# 6LED_controller.net
KiCad netlist of a schematic drawn in EAGLE
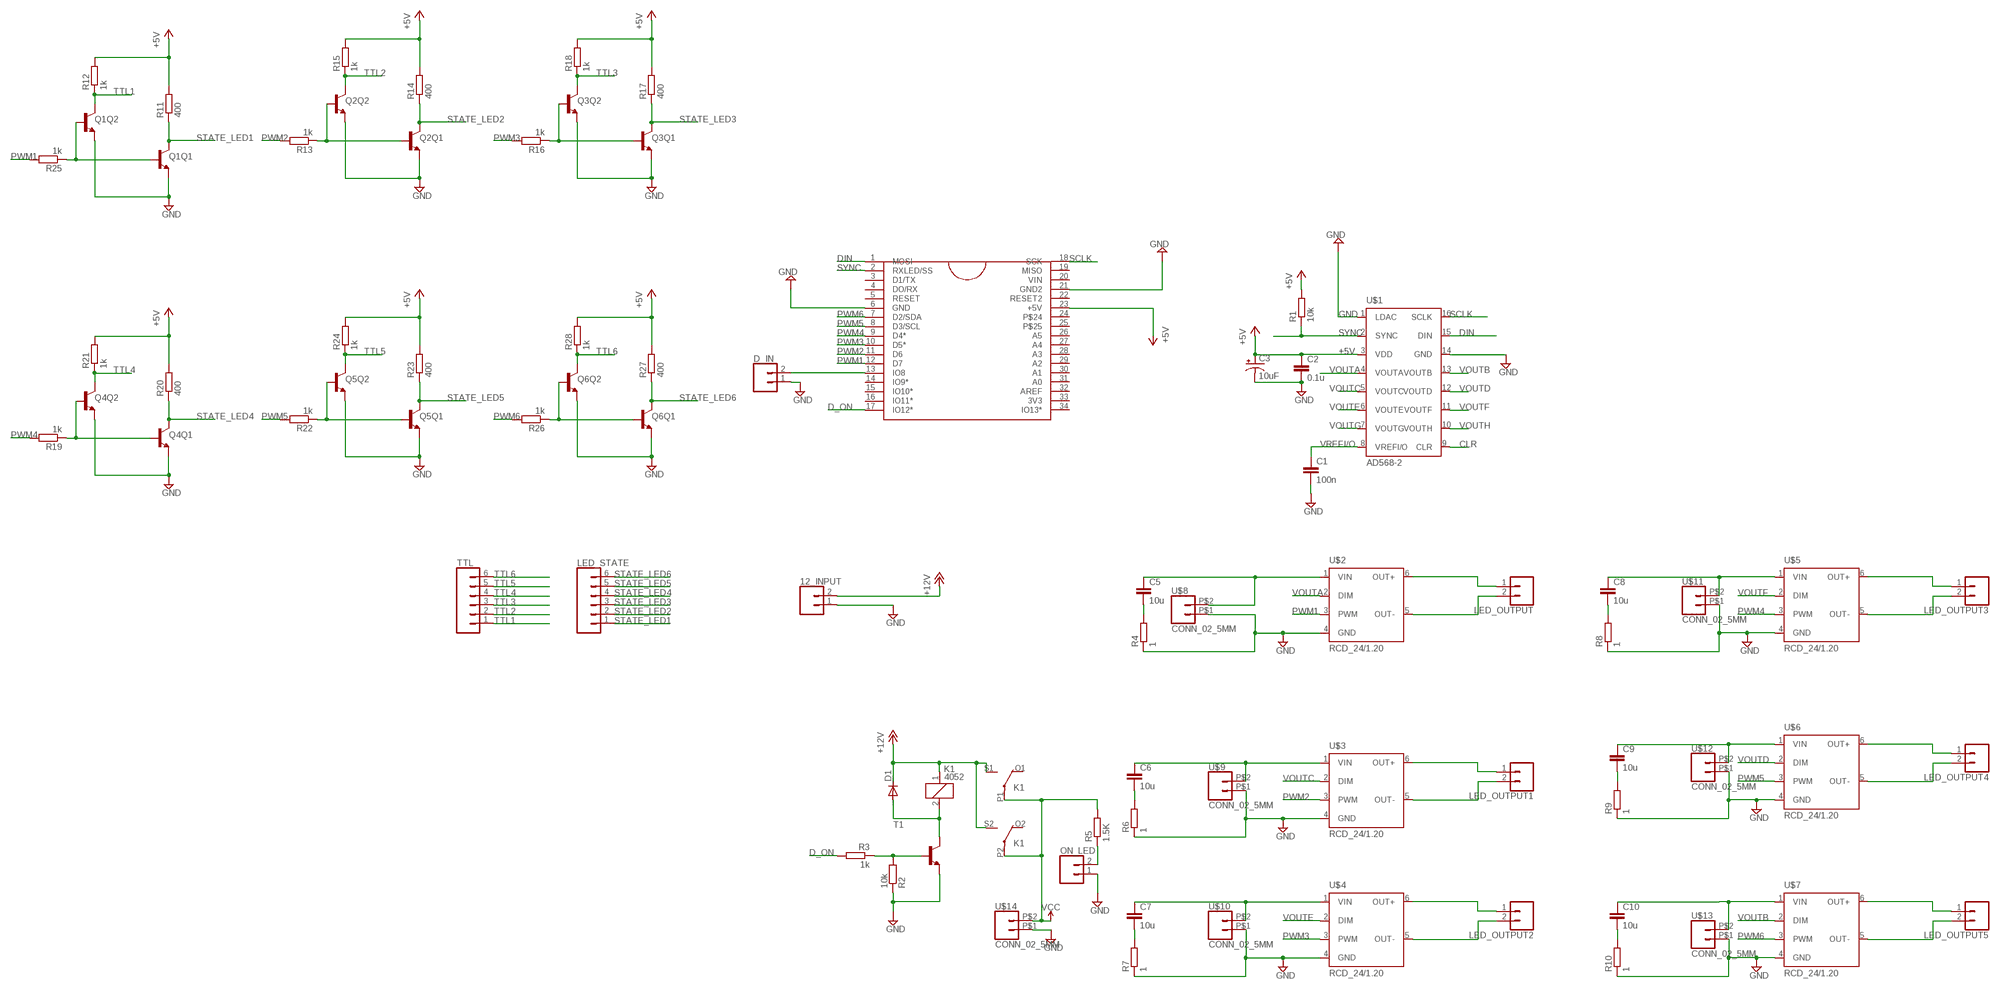
[diagram p0: schematic, sheet 1]

(export (version "E")
  (design (tool "Eeschema 10.0.6"))
  (components
    (comp (ref "12_INPUT")
      (value "CONN_023.5MM")
      (footprint "eagle-import:SCREWTERMINAL-3.5MM-2")
      (libsource (lib "eagle-import") (part "CONN_023.5MM"))
    )
    (comp (ref "C1")
      (value "100n")
      (footprint "eagle-import:C1206")
      (libsource (lib "eagle-import") (part "C-EUC1206"))
    )
    (comp (ref "C2")
      (value "0.1u")
      (footprint "eagle-import:C1206")
      (libsource (lib "eagle-import") (part "C-EUC1206"))
    )
    (comp (ref "C3")
      (value "10uF")
      (footprint "eagle-import:EIA3528")
      (libsource (lib "eagle-import") (part "10UF-POLAR-EIA3528-20V-10%(TANT)"))
    )
    (comp (ref "C5")
      (value "10u")
      (footprint "eagle-import:C1206")
      (libsource (lib "eagle-import") (part "C-EUC1206"))
    )
    (comp (ref "C6")
      (value "10u")
      (footprint "eagle-import:C1206")
      (libsource (lib "eagle-import") (part "C-EUC1206"))
    )
    (comp (ref "C7")
      (value "10u")
      (footprint "eagle-import:C1206")
      (libsource (lib "eagle-import") (part "C-EUC1206"))
    )
    (comp (ref "C8")
      (value "10u")
      (footprint "eagle-import:C1206")
      (libsource (lib "eagle-import") (part "C-EUC1206"))
    )
    (comp (ref "C9")
      (value "10u")
      (footprint "eagle-import:C1206")
      (libsource (lib "eagle-import") (part "C-EUC1206"))
    )
    (comp (ref "C10")
      (value "10u")
      (footprint "eagle-import:C1206")
      (libsource (lib "eagle-import") (part "C-EUC1206"))
    )
    (comp (ref "D1")
      (value "DIODE-DO214AC")
      (footprint "eagle-import:DO214AC")
      (libsource (lib "eagle-import") (part "DIODE-DO214AC"))
    )
    (comp (ref "D_IN")
      (value "CONN_02")
      (footprint "eagle-import:1X02")
      (libsource (lib "eagle-import") (part "CONN_02"))
    )
    (comp (ref "K1")
      (value "4052")
      (footprint "eagle-import:F4052")
      (libsource (lib "eagle-import") (part "4052"))
    )
    (comp (ref "LED_OUTPUT")
      (value "CONN_023.5MM")
      (footprint "eagle-import:SCREWTERMINAL-3.5MM-2")
      (libsource (lib "eagle-import") (part "CONN_023.5MM"))
    )
    (comp (ref "LED_OUTPUT1")
      (value "CONN_023.5MM")
      (footprint "eagle-import:SCREWTERMINAL-3.5MM-2")
      (libsource (lib "eagle-import") (part "CONN_023.5MM"))
    )
    (comp (ref "LED_OUTPUT2")
      (value "CONN_023.5MM")
      (footprint "eagle-import:SCREWTERMINAL-3.5MM-2")
      (libsource (lib "eagle-import") (part "CONN_023.5MM"))
    )
    (comp (ref "LED_OUTPUT3")
      (value "CONN_023.5MM")
      (footprint "eagle-import:SCREWTERMINAL-3.5MM-2")
      (libsource (lib "eagle-import") (part "CONN_023.5MM"))
    )
    (comp (ref "LED_OUTPUT4")
      (value "CONN_023.5MM")
      (footprint "eagle-import:SCREWTERMINAL-3.5MM-2")
      (libsource (lib "eagle-import") (part "CONN_023.5MM"))
    )
    (comp (ref "LED_OUTPUT5")
      (value "CONN_023.5MM")
      (footprint "eagle-import:SCREWTERMINAL-3.5MM-2")
      (libsource (lib "eagle-import") (part "CONN_023.5MM"))
    )
    (comp (ref "LED_STATE")
      (value "CONN_06POLAR")
      (footprint "eagle-import:MOLEX-1X6")
      (libsource (lib "eagle-import") (part "CONN_06POLAR"))
    )
    (comp (ref "ON_LED")
      (value "CONN_02")
      (footprint "eagle-import:1X02")
      (libsource (lib "eagle-import") (part "CONN_02"))
    )
    (comp (ref "Q1")
      (value "TRANS_NPN_DUAL_NSM4002-MBT3904DW1T1")
      (footprint "eagle-import:SC70-6")
      (libsource (lib "eagle-import") (part "TRANS_NPN_DUAL_NSM4002-MBT3904DW1T1"))
    )
    (comp (ref "Q2")
      (value "TRANS_NPN_DUAL_NSM4002-MBT3904DW1T1")
      (footprint "eagle-import:SC70-6")
      (libsource (lib "eagle-import") (part "TRANS_NPN_DUAL_NSM4002-MBT3904DW1T1"))
    )
    (comp (ref "Q3")
      (value "TRANS_NPN_DUAL_NSM4002-MBT3904DW1T1")
      (footprint "eagle-import:SC70-6")
      (libsource (lib "eagle-import") (part "TRANS_NPN_DUAL_NSM4002-MBT3904DW1T1"))
    )
    (comp (ref "Q4")
      (value "TRANS_NPN_DUAL_NSM4002-MBT3904DW1T1")
      (footprint "eagle-import:SC70-6")
      (libsource (lib "eagle-import") (part "TRANS_NPN_DUAL_NSM4002-MBT3904DW1T1"))
    )
    (comp (ref "Q5")
      (value "TRANS_NPN_DUAL_NSM4002-MBT3904DW1T1")
      (footprint "eagle-import:SC70-6")
      (libsource (lib "eagle-import") (part "TRANS_NPN_DUAL_NSM4002-MBT3904DW1T1"))
    )
    (comp (ref "Q6")
      (value "TRANS_NPN_DUAL_NSM4002-MBT3904DW1T1")
      (footprint "eagle-import:SC70-6")
      (libsource (lib "eagle-import") (part "TRANS_NPN_DUAL_NSM4002-MBT3904DW1T1"))
    )
    (comp (ref "R1")
      (value "10k")
      (footprint "eagle-import:R1206")
      (libsource (lib "eagle-import") (part "R-EU_R1206"))
    )
    (comp (ref "R2")
      (value "10k")
      (footprint "eagle-import:R1206")
      (libsource (lib "eagle-import") (part "R-EU_R1206"))
    )
    (comp (ref "R3")
      (value "1k")
      (footprint "eagle-import:R0805")
      (libsource (lib "eagle-import") (part "R-EU_R0805"))
    )
    (comp (ref "R4")
      (value "1")
      (footprint "eagle-import:R2512")
      (libsource (lib "eagle-import") (part "R-EU_R2512"))
    )
    (comp (ref "R5")
      (value "1.5K")
      (footprint "eagle-import:R0805")
      (libsource (lib "eagle-import") (part "R-EU_R0805"))
    )
    (comp (ref "R6")
      (value "1")
      (footprint "eagle-import:R2512")
      (libsource (lib "eagle-import") (part "R-EU_R2512"))
    )
    (comp (ref "R7")
      (value "1")
      (footprint "eagle-import:R2512")
      (libsource (lib "eagle-import") (part "R-EU_R2512"))
    )
    (comp (ref "R8")
      (value "1")
      (footprint "eagle-import:R2512")
      (libsource (lib "eagle-import") (part "R-EU_R2512"))
    )
    (comp (ref "R9")
      (value "1")
      (footprint "eagle-import:R2512")
      (libsource (lib "eagle-import") (part "R-EU_R2512"))
    )
    (comp (ref "R10")
      (value "1")
      (footprint "eagle-import:R2512")
      (libsource (lib "eagle-import") (part "R-EU_R2512"))
    )
    (comp (ref "R11")
      (value "400")
      (footprint "eagle-import:R0805")
      (libsource (lib "eagle-import") (part "R-EU_R0805"))
    )
    (comp (ref "R12")
      (value "1k")
      (footprint "eagle-import:R0805")
      (libsource (lib "eagle-import") (part "R-EU_R0805"))
    )
    (comp (ref "R13")
      (value "1k")
      (footprint "eagle-import:R0805")
      (libsource (lib "eagle-import") (part "R-EU_R0805"))
    )
    (comp (ref "R14")
      (value "400")
      (footprint "eagle-import:R0805")
      (libsource (lib "eagle-import") (part "R-EU_R0805"))
    )
    (comp (ref "R15")
      (value "1k")
      (footprint "eagle-import:R0805")
      (libsource (lib "eagle-import") (part "R-EU_R0805"))
    )
    (comp (ref "R16")
      (value "1k")
      (footprint "eagle-import:R0805")
      (libsource (lib "eagle-import") (part "R-EU_R0805"))
    )
    (comp (ref "R17")
      (value "400")
      (footprint "eagle-import:R0805")
      (libsource (lib "eagle-import") (part "R-EU_R0805"))
    )
    (comp (ref "R18")
      (value "1k")
      (footprint "eagle-import:R0805")
      (libsource (lib "eagle-import") (part "R-EU_R0805"))
    )
    (comp (ref "R19")
      (value "1k")
      (footprint "eagle-import:R0805")
      (libsource (lib "eagle-import") (part "R-EU_R0805"))
    )
    (comp (ref "R20")
      (value "400")
      (footprint "eagle-import:R0805")
      (libsource (lib "eagle-import") (part "R-EU_R0805"))
    )
    (comp (ref "R21")
      (value "1k")
      (footprint "eagle-import:R0805")
      (libsource (lib "eagle-import") (part "R-EU_R0805"))
    )
    (comp (ref "R22")
      (value "1k")
      (footprint "eagle-import:R0805")
      (libsource (lib "eagle-import") (part "R-EU_R0805"))
    )
    (comp (ref "R23")
      (value "400")
      (footprint "eagle-import:R0805")
      (libsource (lib "eagle-import") (part "R-EU_R0805"))
    )
    (comp (ref "R24")
      (value "1k")
      (footprint "eagle-import:R0805")
      (libsource (lib "eagle-import") (part "R-EU_R0805"))
    )
    (comp (ref "R25")
      (value "1k")
      (footprint "eagle-import:R0805")
      (libsource (lib "eagle-import") (part "R-EU_R0805"))
    )
    (comp (ref "R26")
      (value "1k")
      (footprint "eagle-import:R0805")
      (libsource (lib "eagle-import") (part "R-EU_R0805"))
    )
    (comp (ref "R27")
      (value "400")
      (footprint "eagle-import:R0805")
      (libsource (lib "eagle-import") (part "R-EU_R0805"))
    )
    (comp (ref "R28")
      (value "1k")
      (footprint "eagle-import:R0805")
      (libsource (lib "eagle-import") (part "R-EU_R0805"))
    )
    (comp (ref "T1")
      (value "-NPN-SOT223")
      (footprint "eagle-import:SOT223")
      (libsource (lib "eagle-import") (part "-NPN-SOT223"))
    )
    (comp (ref "TTL")
      (value "CONN_06POLAR")
      (footprint "eagle-import:MOLEX-1X6")
      (libsource (lib "eagle-import") (part "CONN_06POLAR"))
    )
    (comp (ref "U$1")
      (value "AD568-2")
      (footprint "eagle-import:TSSOP-16")
      (libsource (lib "eagle-import") (part "AD568-2"))
    )
    (comp (ref "U$2")
      (value "RCD_24/1.20")
      (footprint "eagle-import:RCD-24_W_X3")
      (libsource (lib "eagle-import") (part "RCD_24/1.20"))
    )
    (comp (ref "U$3")
      (value "RCD_24/1.20")
      (footprint "eagle-import:RCD-24_W_X3")
      (libsource (lib "eagle-import") (part "RCD_24/1.20"))
    )
    (comp (ref "U$4")
      (value "RCD_24/1.20")
      (footprint "eagle-import:RCD-24_W_X3")
      (libsource (lib "eagle-import") (part "RCD_24/1.20"))
    )
    (comp (ref "U$5")
      (value "RCD_24/1.20")
      (footprint "eagle-import:RCD-24_W_X3")
      (libsource (lib "eagle-import") (part "RCD_24/1.20"))
    )
    (comp (ref "U$6")
      (value "RCD_24/1.20")
      (footprint "eagle-import:RCD-24_W_X3")
      (libsource (lib "eagle-import") (part "RCD_24/1.20"))
    )
    (comp (ref "U$7")
      (value "RCD_24/1.20")
      (footprint "eagle-import:RCD-24_W_X3")
      (libsource (lib "eagle-import") (part "RCD_24/1.20"))
    )
    (comp (ref "U$8")
      (value "CONN_02_5MM")
      (footprint "eagle-import:1X02_BIG_5MM")
      (libsource (lib "eagle-import") (part "CONN_02_5MM"))
    )
    (comp (ref "U$9")
      (value "CONN_02_5MM")
      (footprint "eagle-import:1X02_BIG_5MM")
      (libsource (lib "eagle-import") (part "CONN_02_5MM"))
    )
    (comp (ref "U$10")
      (value "CONN_02_5MM")
      (footprint "eagle-import:1X02_BIG_5MM")
      (libsource (lib "eagle-import") (part "CONN_02_5MM"))
    )
    (comp (ref "U$11")
      (value "CONN_02_5MM")
      (footprint "eagle-import:1X02_BIG_5MM")
      (libsource (lib "eagle-import") (part "CONN_02_5MM"))
    )
    (comp (ref "U$12")
      (value "CONN_02_5MM")
      (footprint "eagle-import:1X02_BIG_5MM")
      (libsource (lib "eagle-import") (part "CONN_02_5MM"))
    )
    (comp (ref "U$13")
      (value "CONN_02_5MM")
      (footprint "eagle-import:1X02_BIG_5MM")
      (libsource (lib "eagle-import") (part "CONN_02_5MM"))
    )
    (comp (ref "U$14")
      (value "CONN_02_5MM")
      (footprint "eagle-import:1X02_BIG_5MM")
      (libsource (lib "eagle-import") (part "CONN_02_5MM"))
    )
    (comp (ref "U$20")
      (value "ARDUINO_MICRO")
      (footprint "eagle-import:ARDUINO_MICRO_PADS")
      (fields (field (name "SPICEPREFIX") "X"))
      (libsource (lib "eagle-import") (part "ARDUINO_MICRO"))
    )
  )
  (nets
    (net (code "1") (name "+5V") (class "Default")
      (node (ref "C2") (pin "1") (pinfunction "1_1") (pintype "passive"))
      (node (ref "C3") (pin "A") (pinfunction "+_A") (pintype "passive"))
      (node (ref "R1") (pin "2") (pinfunction "2_2") (pintype "passive"))
      (node (ref "R11") (pin "2") (pinfunction "2_2") (pintype "passive"))
      (node (ref "R12") (pin "2") (pinfunction "2_2") (pintype "passive"))
      (node (ref "R14") (pin "2") (pinfunction "2_2") (pintype "passive"))
      (node (ref "R15") (pin "2") (pinfunction "2_2") (pintype "passive"))
      (node (ref "R17") (pin "2") (pinfunction "2_2") (pintype "passive"))
      (node (ref "R18") (pin "2") (pinfunction "2_2") (pintype "passive"))
      (node (ref "R20") (pin "2") (pinfunction "2_2") (pintype "passive"))
      (node (ref "R21") (pin "2") (pinfunction "2_2") (pintype "passive"))
      (node (ref "R23") (pin "2") (pinfunction "2_2") (pintype "passive"))
      (node (ref "R24") (pin "2") (pinfunction "2_2") (pintype "passive"))
      (node (ref "R27") (pin "2") (pinfunction "2_2") (pintype "passive"))
      (node (ref "R28") (pin "2") (pinfunction "2_2") (pintype "passive"))
      (node (ref "U$1") (pin "3") (pinfunction "VDD_3") (pintype "power_in"))
      (node (ref "U$20") (pin "23") (pinfunction "+5V_23") (pintype "bidirectional"))
    )
    (net (code "2") (name "+12V") (class "Default")
      (node (ref "12_INPUT") (pin "2") (pinfunction "2_2") (pintype "passive"))
      (node (ref "D1") (pin "C") (pinfunction "C_C") (pintype "passive"))
      (node (ref "K1") (pin "1") (pinfunction "1_1") (pintype "passive"))
      (node (ref "K1") (pin "S1") (pinfunction "S_S1") (pintype "passive"))
      (node (ref "K1") (pin "S2") (pinfunction "S_S2") (pintype "passive"))
    )
    (net (code "3") (name "/CLR") (class "Default")
      (node (ref "U$1") (pin "9") (pinfunction "CLR_9") (pintype "output"))
    )
    (net (code "4") (name "/DIN") (class "Default")
      (node (ref "U$1") (pin "15") (pinfunction "DIN_15") (pintype "input"))
      (node (ref "U$20") (pin "1") (pinfunction "MOSI_1") (pintype "bidirectional"))
    )
    (net (code "5") (name "/D_ON") (class "Default")
      (node (ref "R3") (pin "2") (pinfunction "2_2") (pintype "passive"))
      (node (ref "U$20") (pin "17") (pinfunction "IO12*_17") (pintype "bidirectional"))
    )
    (net (code "6") (name "/PWM1") (class "Default")
      (node (ref "R25") (pin "2") (pinfunction "2_2") (pintype "passive"))
      (node (ref "U$2") (pin "3") (pinfunction "PWM_3") (pintype "passive"))
      (node (ref "U$20") (pin "12") (pinfunction "D7_12") (pintype "bidirectional"))
    )
    (net (code "7") (name "/PWM2") (class "Default")
      (node (ref "R13") (pin "2") (pinfunction "2_2") (pintype "passive"))
      (node (ref "U$20") (pin "11") (pinfunction "D6_11") (pintype "bidirectional"))
      (node (ref "U$3") (pin "3") (pinfunction "PWM_3") (pintype "passive"))
    )
    (net (code "8") (name "/PWM3") (class "Default")
      (node (ref "R16") (pin "2") (pinfunction "2_2") (pintype "passive"))
      (node (ref "U$20") (pin "10") (pinfunction "D5*_10") (pintype "bidirectional"))
      (node (ref "U$4") (pin "3") (pinfunction "PWM_3") (pintype "passive"))
    )
    (net (code "9") (name "/PWM4") (class "Default")
      (node (ref "R19") (pin "2") (pinfunction "2_2") (pintype "passive"))
      (node (ref "U$20") (pin "9") (pinfunction "D4*_9") (pintype "bidirectional"))
      (node (ref "U$5") (pin "3") (pinfunction "PWM_3") (pintype "passive"))
    )
    (net (code "10") (name "/PWM5") (class "Default")
      (node (ref "R22") (pin "2") (pinfunction "2_2") (pintype "passive"))
      (node (ref "U$20") (pin "8") (pinfunction "D3/SCL_8") (pintype "bidirectional"))
      (node (ref "U$6") (pin "3") (pinfunction "PWM_3") (pintype "passive"))
    )
    (net (code "11") (name "/PWM6") (class "Default")
      (node (ref "R26") (pin "2") (pinfunction "2_2") (pintype "passive"))
      (node (ref "U$20") (pin "7") (pinfunction "D2/SDA_7") (pintype "bidirectional"))
      (node (ref "U$7") (pin "3") (pinfunction "PWM_3") (pintype "passive"))
    )
    (net (code "12") (name "/SCLK") (class "Default")
      (node (ref "U$1") (pin "16") (pinfunction "SCLK_16") (pintype "input"))
      (node (ref "U$20") (pin "18") (pinfunction "SCK_18") (pintype "bidirectional"))
    )
    (net (code "13") (name "/STATE_LED1") (class "Default")
      (node (ref "LED_STATE") (pin "1") (pinfunction "1_1") (pintype "passive"))
      (node (ref "Q1") (pin "3") (pinfunction "C_3") (pintype "passive"))
      (node (ref "R11") (pin "1") (pinfunction "1_1") (pintype "passive"))
    )
    (net (code "14") (name "/STATE_LED2") (class "Default")
      (node (ref "LED_STATE") (pin "2") (pinfunction "2_2") (pintype "passive"))
      (node (ref "Q2") (pin "3") (pinfunction "C_3") (pintype "passive"))
      (node (ref "R14") (pin "1") (pinfunction "1_1") (pintype "passive"))
    )
    (net (code "15") (name "/STATE_LED3") (class "Default")
      (node (ref "LED_STATE") (pin "3") (pinfunction "3_3") (pintype "passive"))
      (node (ref "Q3") (pin "3") (pinfunction "C_3") (pintype "passive"))
      (node (ref "R17") (pin "1") (pinfunction "1_1") (pintype "passive"))
    )
    (net (code "16") (name "/STATE_LED4") (class "Default")
      (node (ref "LED_STATE") (pin "4") (pinfunction "4_4") (pintype "passive"))
      (node (ref "Q4") (pin "3") (pinfunction "C_3") (pintype "passive"))
      (node (ref "R20") (pin "1") (pinfunction "1_1") (pintype "passive"))
    )
    (net (code "17") (name "/STATE_LED5") (class "Default")
      (node (ref "LED_STATE") (pin "5") (pinfunction "5_5") (pintype "passive"))
      (node (ref "Q5") (pin "3") (pinfunction "C_3") (pintype "passive"))
      (node (ref "R23") (pin "1") (pinfunction "1_1") (pintype "passive"))
    )
    (net (code "18") (name "/STATE_LED6") (class "Default")
      (node (ref "LED_STATE") (pin "6") (pinfunction "6_6") (pintype "passive"))
      (node (ref "Q6") (pin "3") (pinfunction "C_3") (pintype "passive"))
      (node (ref "R27") (pin "1") (pinfunction "1_1") (pintype "passive"))
    )
    (net (code "19") (name "/SYNC") (class "Default")
      (node (ref "R1") (pin "1") (pinfunction "1_1") (pintype "passive"))
      (node (ref "U$1") (pin "2") (pinfunction "SYNC_2") (pintype "input"))
      (node (ref "U$20") (pin "2") (pinfunction "RXLED/SS_2") (pintype "bidirectional"))
    )
    (net (code "20") (name "/TTL1") (class "Default")
      (node (ref "Q1") (pin "6") (pinfunction "C_6") (pintype "passive"))
      (node (ref "R12") (pin "1") (pinfunction "1_1") (pintype "passive"))
      (node (ref "TTL") (pin "1") (pinfunction "1_1") (pintype "passive"))
    )
    (net (code "21") (name "/TTL2") (class "Default")
      (node (ref "Q2") (pin "6") (pinfunction "C_6") (pintype "passive"))
      (node (ref "R15") (pin "1") (pinfunction "1_1") (pintype "passive"))
      (node (ref "TTL") (pin "2") (pinfunction "2_2") (pintype "passive"))
    )
    (net (code "22") (name "/TTL3") (class "Default")
      (node (ref "Q3") (pin "6") (pinfunction "C_6") (pintype "passive"))
      (node (ref "R18") (pin "1") (pinfunction "1_1") (pintype "passive"))
      (node (ref "TTL") (pin "3") (pinfunction "3_3") (pintype "passive"))
    )
    (net (code "23") (name "/TTL4") (class "Default")
      (node (ref "Q4") (pin "6") (pinfunction "C_6") (pintype "passive"))
      (node (ref "R21") (pin "1") (pinfunction "1_1") (pintype "passive"))
      (node (ref "TTL") (pin "4") (pinfunction "4_4") (pintype "passive"))
    )
    (net (code "24") (name "/TTL5") (class "Default")
      (node (ref "Q5") (pin "6") (pinfunction "C_6") (pintype "passive"))
      (node (ref "R24") (pin "1") (pinfunction "1_1") (pintype "passive"))
      (node (ref "TTL") (pin "5") (pinfunction "5_5") (pintype "passive"))
    )
    (net (code "25") (name "/TTL6") (class "Default")
      (node (ref "Q6") (pin "6") (pinfunction "C_6") (pintype "passive"))
      (node (ref "R28") (pin "1") (pinfunction "1_1") (pintype "passive"))
      (node (ref "TTL") (pin "6") (pinfunction "6_6") (pintype "passive"))
    )
    (net (code "26") (name "/VOUTA") (class "Default")
      (node (ref "U$1") (pin "4") (pinfunction "VOUTA_4") (pintype "output"))
      (node (ref "U$2") (pin "2") (pinfunction "DIM_2") (pintype "passive"))
    )
    (net (code "27") (name "/VOUTB") (class "Default")
      (node (ref "U$1") (pin "13") (pinfunction "VOUTB_13") (pintype "output"))
      (node (ref "U$7") (pin "2") (pinfunction "DIM_2") (pintype "passive"))
    )
    (net (code "28") (name "/VOUTC") (class "Default")
      (node (ref "U$1") (pin "5") (pinfunction "VOUTC_5") (pintype "output"))
      (node (ref "U$3") (pin "2") (pinfunction "DIM_2") (pintype "passive"))
    )
    (net (code "29") (name "/VOUTD") (class "Default")
      (node (ref "U$1") (pin "12") (pinfunction "VOUTD_12") (pintype "output"))
      (node (ref "U$6") (pin "2") (pinfunction "DIM_2") (pintype "passive"))
    )
    (net (code "30") (name "/VOUTE") (class "Default")
      (node (ref "U$1") (pin "6") (pinfunction "VOUTE_6") (pintype "output"))
      (node (ref "U$4") (pin "2") (pinfunction "DIM_2") (pintype "passive"))
    )
    (net (code "31") (name "/VOUTF") (class "Default")
      (node (ref "U$1") (pin "11") (pinfunction "VOUTF_11") (pintype "output"))
      (node (ref "U$5") (pin "2") (pinfunction "DIM_2") (pintype "passive"))
    )
    (net (code "32") (name "/VOUTG") (class "Default")
      (node (ref "U$1") (pin "7") (pinfunction "VOUTG_7") (pintype "output"))
    )
    (net (code "33") (name "/VOUTH") (class "Default")
      (node (ref "U$1") (pin "10") (pinfunction "VOUTH_10") (pintype "output"))
    )
    (net (code "34") (name "/VREFI{slash}O") (class "Default")
      (node (ref "C1") (pin "1") (pinfunction "1_1") (pintype "passive"))
      (node (ref "U$1") (pin "8") (pinfunction "VREFI/O_8") (pintype "output"))
    )
    (net (code "35") (name "GND") (class "Default")
      (node (ref "12_INPUT") (pin "1") (pinfunction "1_1") (pintype "passive"))
      (node (ref "C1") (pin "2") (pinfunction "2_2") (pintype "passive"))
      (node (ref "C2") (pin "2") (pinfunction "2_2") (pintype "passive"))
      (node (ref "C3") (pin "C") (pinfunction "-_C") (pintype "passive"))
      (node (ref "D_IN") (pin "1") (pinfunction "1_1") (pintype "passive"))
      (node (ref "ON_LED") (pin "1") (pinfunction "1_1") (pintype "passive"))
      (node (ref "Q1") (pin "1") (pinfunction "E_1") (pintype "passive"))
      (node (ref "Q1") (pin "4") (pinfunction "E_4") (pintype "passive"))
      (node (ref "Q2") (pin "1") (pinfunction "E_1") (pintype "passive"))
      (node (ref "Q2") (pin "4") (pinfunction "E_4") (pintype "passive"))
      (node (ref "Q3") (pin "1") (pinfunction "E_1") (pintype "passive"))
      (node (ref "Q3") (pin "4") (pinfunction "E_4") (pintype "passive"))
      (node (ref "Q4") (pin "1") (pinfunction "E_1") (pintype "passive"))
      (node (ref "Q4") (pin "4") (pinfunction "E_4") (pintype "passive"))
      (node (ref "Q5") (pin "1") (pinfunction "E_1") (pintype "passive"))
      (node (ref "Q5") (pin "4") (pinfunction "E_4") (pintype "passive"))
      (node (ref "Q6") (pin "1") (pinfunction "E_1") (pintype "passive"))
      (node (ref "Q6") (pin "4") (pinfunction "E_4") (pintype "passive"))
      (node (ref "R10") (pin "1") (pinfunction "1_1") (pintype "passive"))
      (node (ref "R2") (pin "1") (pinfunction "1_1") (pintype "passive"))
      (node (ref "R4") (pin "1") (pinfunction "1_1") (pintype "passive"))
      (node (ref "R6") (pin "1") (pinfunction "1_1") (pintype "passive"))
      (node (ref "R7") (pin "1") (pinfunction "1_1") (pintype "passive"))
      (node (ref "R8") (pin "1") (pinfunction "1_1") (pintype "passive"))
      (node (ref "R9") (pin "1") (pinfunction "1_1") (pintype "passive"))
      (node (ref "T1") (pin "3") (pinfunction "E_3") (pintype "passive"))
      (node (ref "U$1") (pin "1") (pinfunction "LDAC_1") (pintype "bidirectional"))
      (node (ref "U$1") (pin "14") (pinfunction "GND_14") (pintype "power_in"))
      (node (ref "U$10") (pin "P$1") (pinfunction "1_P$1") (pintype "passive"))
      (node (ref "U$11") (pin "P$1") (pinfunction "1_P$1") (pintype "passive"))
      (node (ref "U$12") (pin "P$1") (pinfunction "1_P$1") (pintype "passive"))
      (node (ref "U$13") (pin "P$1") (pinfunction "1_P$1") (pintype "passive"))
      (node (ref "U$14") (pin "P$1") (pinfunction "1_P$1") (pintype "passive"))
      (node (ref "U$2") (pin "4") (pinfunction "GND_4") (pintype "power_in"))
      (node (ref "U$20") (pin "21") (pinfunction "GND2_21") (pintype "power_in"))
      (node (ref "U$20") (pin "6") (pinfunction "GND_6") (pintype "power_in"))
      (node (ref "U$3") (pin "4") (pinfunction "GND_4") (pintype "power_in"))
      (node (ref "U$4") (pin "4") (pinfunction "GND_4") (pintype "power_in"))
      (node (ref "U$5") (pin "4") (pinfunction "GND_4") (pintype "power_in"))
      (node (ref "U$6") (pin "4") (pinfunction "GND_4") (pintype "power_in"))
      (node (ref "U$7") (pin "4") (pinfunction "GND_4") (pintype "power_in"))
      (node (ref "U$8") (pin "P$1") (pinfunction "1_P$1") (pintype "passive"))
      (node (ref "U$9") (pin "P$1") (pinfunction "1_P$1") (pintype "passive"))
    )
    (net (code "36") (name "Net-(C5-Pad2)") (class "Default")
      (node (ref "C5") (pin "2") (pinfunction "2_2") (pintype "passive"))
      (node (ref "R4") (pin "2") (pinfunction "2_2") (pintype "passive"))
    )
    (net (code "37") (name "Net-(C6-Pad2)") (class "Default")
      (node (ref "C6") (pin "2") (pinfunction "2_2") (pintype "passive"))
      (node (ref "R6") (pin "2") (pinfunction "2_2") (pintype "passive"))
    )
    (net (code "38") (name "Net-(C7-Pad2)") (class "Default")
      (node (ref "C7") (pin "2") (pinfunction "2_2") (pintype "passive"))
      (node (ref "R7") (pin "2") (pinfunction "2_2") (pintype "passive"))
    )
    (net (code "39") (name "Net-(C8-Pad2)") (class "Default")
      (node (ref "C8") (pin "2") (pinfunction "2_2") (pintype "passive"))
      (node (ref "R8") (pin "2") (pinfunction "2_2") (pintype "passive"))
    )
    (net (code "40") (name "Net-(C9-Pad2)") (class "Default")
      (node (ref "C9") (pin "2") (pinfunction "2_2") (pintype "passive"))
      (node (ref "R9") (pin "2") (pinfunction "2_2") (pintype "passive"))
    )
    (net (code "41") (name "Net-(C10-Pad2)") (class "Default")
      (node (ref "C10") (pin "2") (pinfunction "2_2") (pintype "passive"))
      (node (ref "R10") (pin "2") (pinfunction "2_2") (pintype "passive"))
    )
    (net (code "42") (name "Net-(ON_LED-Pad2)") (class "Default")
      (node (ref "ON_LED") (pin "2") (pinfunction "2_2") (pintype "passive"))
      (node (ref "R5") (pin "1") (pinfunction "1_1") (pintype "passive"))
    )
    (net (code "43") (name "Net-(Q1A-B)") (class "Default")
      (node (ref "Q1") (pin "2") (pinfunction "B_2") (pintype "passive"))
      (node (ref "Q1") (pin "5") (pinfunction "B_5") (pintype "passive"))
      (node (ref "R25") (pin "1") (pinfunction "1_1") (pintype "passive"))
    )
    (net (code "44") (name "Net-(Q2A-B)") (class "Default")
      (node (ref "Q2") (pin "2") (pinfunction "B_2") (pintype "passive"))
      (node (ref "Q2") (pin "5") (pinfunction "B_5") (pintype "passive"))
      (node (ref "R13") (pin "1") (pinfunction "1_1") (pintype "passive"))
    )
    (net (code "45") (name "Net-(Q3A-B)") (class "Default")
      (node (ref "Q3") (pin "2") (pinfunction "B_2") (pintype "passive"))
      (node (ref "Q3") (pin "5") (pinfunction "B_5") (pintype "passive"))
      (node (ref "R16") (pin "1") (pinfunction "1_1") (pintype "passive"))
    )
    (net (code "46") (name "Net-(Q4A-B)") (class "Default")
      (node (ref "Q4") (pin "2") (pinfunction "B_2") (pintype "passive"))
      (node (ref "Q4") (pin "5") (pinfunction "B_5") (pintype "passive"))
      (node (ref "R19") (pin "1") (pinfunction "1_1") (pintype "passive"))
    )
    (net (code "47") (name "Net-(Q5A-B)") (class "Default")
      (node (ref "Q5") (pin "2") (pinfunction "B_2") (pintype "passive"))
      (node (ref "Q5") (pin "5") (pinfunction "B_5") (pintype "passive"))
      (node (ref "R22") (pin "1") (pinfunction "1_1") (pintype "passive"))
    )
    (net (code "48") (name "Net-(Q6A-B)") (class "Default")
      (node (ref "Q6") (pin "2") (pinfunction "B_2") (pintype "passive"))
      (node (ref "Q6") (pin "5") (pinfunction "B_5") (pintype "passive"))
      (node (ref "R26") (pin "1") (pinfunction "1_1") (pintype "passive"))
    )
    (net (code "49") (name "Net-(T1-B)") (class "Default")
      (node (ref "R2") (pin "2") (pinfunction "2_2") (pintype "passive"))
      (node (ref "R3") (pin "1") (pinfunction "1_1") (pintype "passive"))
      (node (ref "T1") (pin "1") (pinfunction "B_1") (pintype "passive"))
    )
    (net (code "50") (name "Net-(T1-C)") (class "Default")
      (node (ref "D1") (pin "A") (pinfunction "A_A") (pintype "passive"))
      (node (ref "K1") (pin "2") (pinfunction "2_2") (pintype "passive"))
      (node (ref "T1") (pin "4") (pinfunction "C_4") (pintype "passive"))
    )
    (net (code "51") (name "Net-(U$2-OUT+)") (class "Default")
      (node (ref "LED_OUTPUT") (pin "1") (pinfunction "1_1") (pintype "passive"))
      (node (ref "U$2") (pin "6") (pinfunction "OUT+_6") (pintype "output"))
    )
    (net (code "52") (name "Net-(U$2-OUT-)") (class "Default")
      (node (ref "LED_OUTPUT") (pin "2") (pinfunction "2_2") (pintype "passive"))
      (node (ref "U$2") (pin "5") (pinfunction "OUT-_5") (pintype "output"))
    )
    (net (code "53") (name "Net-(U$2-VIN)") (class "Default")
      (node (ref "C5") (pin "1") (pinfunction "1_1") (pintype "passive"))
      (node (ref "U$2") (pin "1") (pinfunction "VIN_1") (pintype "input"))
      (node (ref "U$8") (pin "P$2") (pinfunction "2_P$2") (pintype "passive"))
    )
    (net (code "54") (name "Net-(U$3-OUT+)") (class "Default")
      (node (ref "LED_OUTPUT1") (pin "1") (pinfunction "1_1") (pintype "passive"))
      (node (ref "U$3") (pin "6") (pinfunction "OUT+_6") (pintype "output"))
    )
    (net (code "55") (name "Net-(U$3-OUT-)") (class "Default")
      (node (ref "LED_OUTPUT1") (pin "2") (pinfunction "2_2") (pintype "passive"))
      (node (ref "U$3") (pin "5") (pinfunction "OUT-_5") (pintype "output"))
    )
    (net (code "56") (name "Net-(U$3-VIN)") (class "Default")
      (node (ref "C6") (pin "1") (pinfunction "1_1") (pintype "passive"))
      (node (ref "U$3") (pin "1") (pinfunction "VIN_1") (pintype "input"))
      (node (ref "U$9") (pin "P$2") (pinfunction "2_P$2") (pintype "passive"))
    )
    (net (code "57") (name "Net-(U$4-OUT+)") (class "Default")
      (node (ref "LED_OUTPUT2") (pin "1") (pinfunction "1_1") (pintype "passive"))
      (node (ref "U$4") (pin "6") (pinfunction "OUT+_6") (pintype "output"))
    )
    (net (code "58") (name "Net-(U$4-OUT-)") (class "Default")
      (node (ref "LED_OUTPUT2") (pin "2") (pinfunction "2_2") (pintype "passive"))
      (node (ref "U$4") (pin "5") (pinfunction "OUT-_5") (pintype "output"))
    )
    (net (code "59") (name "Net-(U$5-OUT+)") (class "Default")
      (node (ref "LED_OUTPUT3") (pin "1") (pinfunction "1_1") (pintype "passive"))
      (node (ref "U$5") (pin "6") (pinfunction "OUT+_6") (pintype "output"))
    )
    (net (code "60") (name "Net-(U$5-OUT-)") (class "Default")
      (node (ref "LED_OUTPUT3") (pin "2") (pinfunction "2_2") (pintype "passive"))
      (node (ref "U$5") (pin "5") (pinfunction "OUT-_5") (pintype "output"))
    )
    (net (code "61") (name "Net-(U$6-OUT+)") (class "Default")
      (node (ref "LED_OUTPUT4") (pin "1") (pinfunction "1_1") (pintype "passive"))
      (node (ref "U$6") (pin "6") (pinfunction "OUT+_6") (pintype "output"))
    )
    (net (code "62") (name "Net-(U$6-OUT-)") (class "Default")
      (node (ref "LED_OUTPUT4") (pin "2") (pinfunction "2_2") (pintype "passive"))
      (node (ref "U$6") (pin "5") (pinfunction "OUT-_5") (pintype "output"))
    )
    (net (code "63") (name "Net-(U$7-OUT+)") (class "Default")
      (node (ref "LED_OUTPUT5") (pin "1") (pinfunction "1_1") (pintype "passive"))
      (node (ref "U$7") (pin "6") (pinfunction "OUT+_6") (pintype "output"))
    )
    (net (code "64") (name "Net-(U$7-OUT-)") (class "Default")
      (node (ref "LED_OUTPUT5") (pin "2") (pinfunction "2_2") (pintype "passive"))
      (node (ref "U$7") (pin "5") (pinfunction "OUT-_5") (pintype "output"))
    )
    (net (code "65") (name "Net-(U$10-2)") (class "Default")
      (node (ref "C7") (pin "1") (pinfunction "1_1") (pintype "passive"))
      (node (ref "U$10") (pin "P$2") (pinfunction "2_P$2") (pintype "passive"))
      (node (ref "U$4") (pin "1") (pinfunction "VIN_1") (pintype "input"))
    )
    (net (code "66") (name "Net-(U$11-2)") (class "Default")
      (node (ref "C8") (pin "1") (pinfunction "1_1") (pintype "passive"))
      (node (ref "U$11") (pin "P$2") (pinfunction "2_P$2") (pintype "passive"))
      (node (ref "U$5") (pin "1") (pinfunction "VIN_1") (pintype "input"))
    )
    (net (code "67") (name "Net-(U$12-2)") (class "Default")
      (node (ref "C9") (pin "1") (pinfunction "1_1") (pintype "passive"))
      (node (ref "U$12") (pin "P$2") (pinfunction "2_P$2") (pintype "passive"))
      (node (ref "U$6") (pin "1") (pinfunction "VIN_1") (pintype "input"))
    )
    (net (code "68") (name "Net-(U$13-2)") (class "Default")
      (node (ref "C10") (pin "1") (pinfunction "1_1") (pintype "passive"))
      (node (ref "U$13") (pin "P$2") (pinfunction "2_P$2") (pintype "passive"))
      (node (ref "U$7") (pin "1") (pinfunction "VIN_1") (pintype "input"))
    )
    (net (code "69") (name "Net-(U$20-IO8)") (class "Default")
      (node (ref "D_IN") (pin "2") (pinfunction "2_2") (pintype "passive"))
      (node (ref "U$20") (pin "13") (pinfunction "IO8_13") (pintype "bidirectional"))
    )
    (net (code "70") (name "VCC") (class "Default")
      (node (ref "K1") (pin "P1") (pinfunction "P_P1") (pintype "passive"))
      (node (ref "K1") (pin "P2") (pinfunction "P_P2") (pintype "passive"))
      (node (ref "R5") (pin "2") (pinfunction "2_2") (pintype "passive"))
      (node (ref "U$14") (pin "P$2") (pinfunction "2_P$2") (pintype "passive"))
    )
    (net (code "71") (name "unconnected-(K1B-O-PadO1)") (class "Default")
      (node (ref "K1") (pin "O1") (pinfunction "O_O1") (pintype "passive"))
    )
    (net (code "72") (name "unconnected-(K1C-O-PadO2)") (class "Default")
      (node (ref "K1") (pin "O2") (pinfunction "O_O2") (pintype "passive"))
    )
    (net (code "73") (name "unconnected-(U$20-3V3-Pad33)") (class "Default")
      (node (ref "U$20") (pin "33") (pinfunction "3V3_33") (pintype "bidirectional"))
    )
    (net (code "74") (name "unconnected-(U$20-A0-Pad31)") (class "Default")
      (node (ref "U$20") (pin "31") (pinfunction "A0_31") (pintype "bidirectional"))
    )
    (net (code "75") (name "unconnected-(U$20-A1-Pad30)") (class "Default")
      (node (ref "U$20") (pin "30") (pinfunction "A1_30") (pintype "bidirectional"))
    )
    (net (code "76") (name "unconnected-(U$20-A2-Pad29)") (class "Default")
      (node (ref "U$20") (pin "29") (pinfunction "A2_29") (pintype "bidirectional"))
    )
    (net (code "77") (name "unconnected-(U$20-A3-Pad28)") (class "Default")
      (node (ref "U$20") (pin "28") (pinfunction "A3_28") (pintype "bidirectional"))
    )
    (net (code "78") (name "unconnected-(U$20-A4-Pad27)") (class "Default")
      (node (ref "U$20") (pin "27") (pinfunction "A4_27") (pintype "bidirectional"))
    )
    (net (code "79") (name "unconnected-(U$20-A5-Pad26)") (class "Default")
      (node (ref "U$20") (pin "26") (pinfunction "A5_26") (pintype "bidirectional"))
    )
    (net (code "80") (name "unconnected-(U$20-AREF-Pad32)") (class "Default")
      (node (ref "U$20") (pin "32") (pinfunction "AREF_32") (pintype "bidirectional"))
    )
    (net (code "81") (name "unconnected-(U$20-D1{slash}TX-Pad3)") (class "Default")
      (node (ref "U$20") (pin "3") (pinfunction "D1/TX_3") (pintype "bidirectional"))
    )
    (net (code "82") (name "unconnected-(U$20-DO{slash}RX-Pad4)") (class "Default")
      (node (ref "U$20") (pin "4") (pinfunction "DO/RX_4") (pintype "bidirectional"))
    )
    (net (code "83") (name "unconnected-(U$20-IO9*-Pad14)") (class "Default")
      (node (ref "U$20") (pin "14") (pinfunction "IO9*_14") (pintype "bidirectional"))
    )
    (net (code "84") (name "unconnected-(U$20-IO10*-Pad15)") (class "Default")
      (node (ref "U$20") (pin "15") (pinfunction "IO10*_15") (pintype "bidirectional"))
    )
    (net (code "85") (name "unconnected-(U$20-IO11*-Pad16)") (class "Default")
      (node (ref "U$20") (pin "16") (pinfunction "IO11*_16") (pintype "bidirectional"))
    )
    (net (code "86") (name "unconnected-(U$20-IO13*-Pad34)") (class "Default")
      (node (ref "U$20") (pin "34") (pinfunction "IO13*_34") (pintype "bidirectional"))
    )
    (net (code "87") (name "unconnected-(U$20-MISO-Pad19)") (class "Default")
      (node (ref "U$20") (pin "19") (pinfunction "MISO_19") (pintype "bidirectional"))
    )
    (net (code "88") (name "unconnected-(U$20-P$24-Pad24)") (class "Default")
      (node (ref "U$20") (pin "24") (pinfunction "P$24_24") (pintype "bidirectional"))
    )
    (net (code "89") (name "unconnected-(U$20-P$25-Pad25)") (class "Default")
      (node (ref "U$20") (pin "25") (pinfunction "P$25_25") (pintype "bidirectional"))
    )
    (net (code "90") (name "unconnected-(U$20-RESET-Pad5)") (class "Default")
      (node (ref "U$20") (pin "5") (pinfunction "RESET_5") (pintype "bidirectional"))
    )
    (net (code "91") (name "unconnected-(U$20-RESET2-Pad22)") (class "Default")
      (node (ref "U$20") (pin "22") (pinfunction "RESET2_22") (pintype "bidirectional"))
    )
    (net (code "92") (name "unconnected-(U$20-VIN-Pad20)") (class "Default")
      (node (ref "U$20") (pin "20") (pinfunction "VIN_20") (pintype "bidirectional"))
    )
  )
)
